# MoteinoR5USB-LP.net
KiCad netlist of a schematic drawn in EAGLE
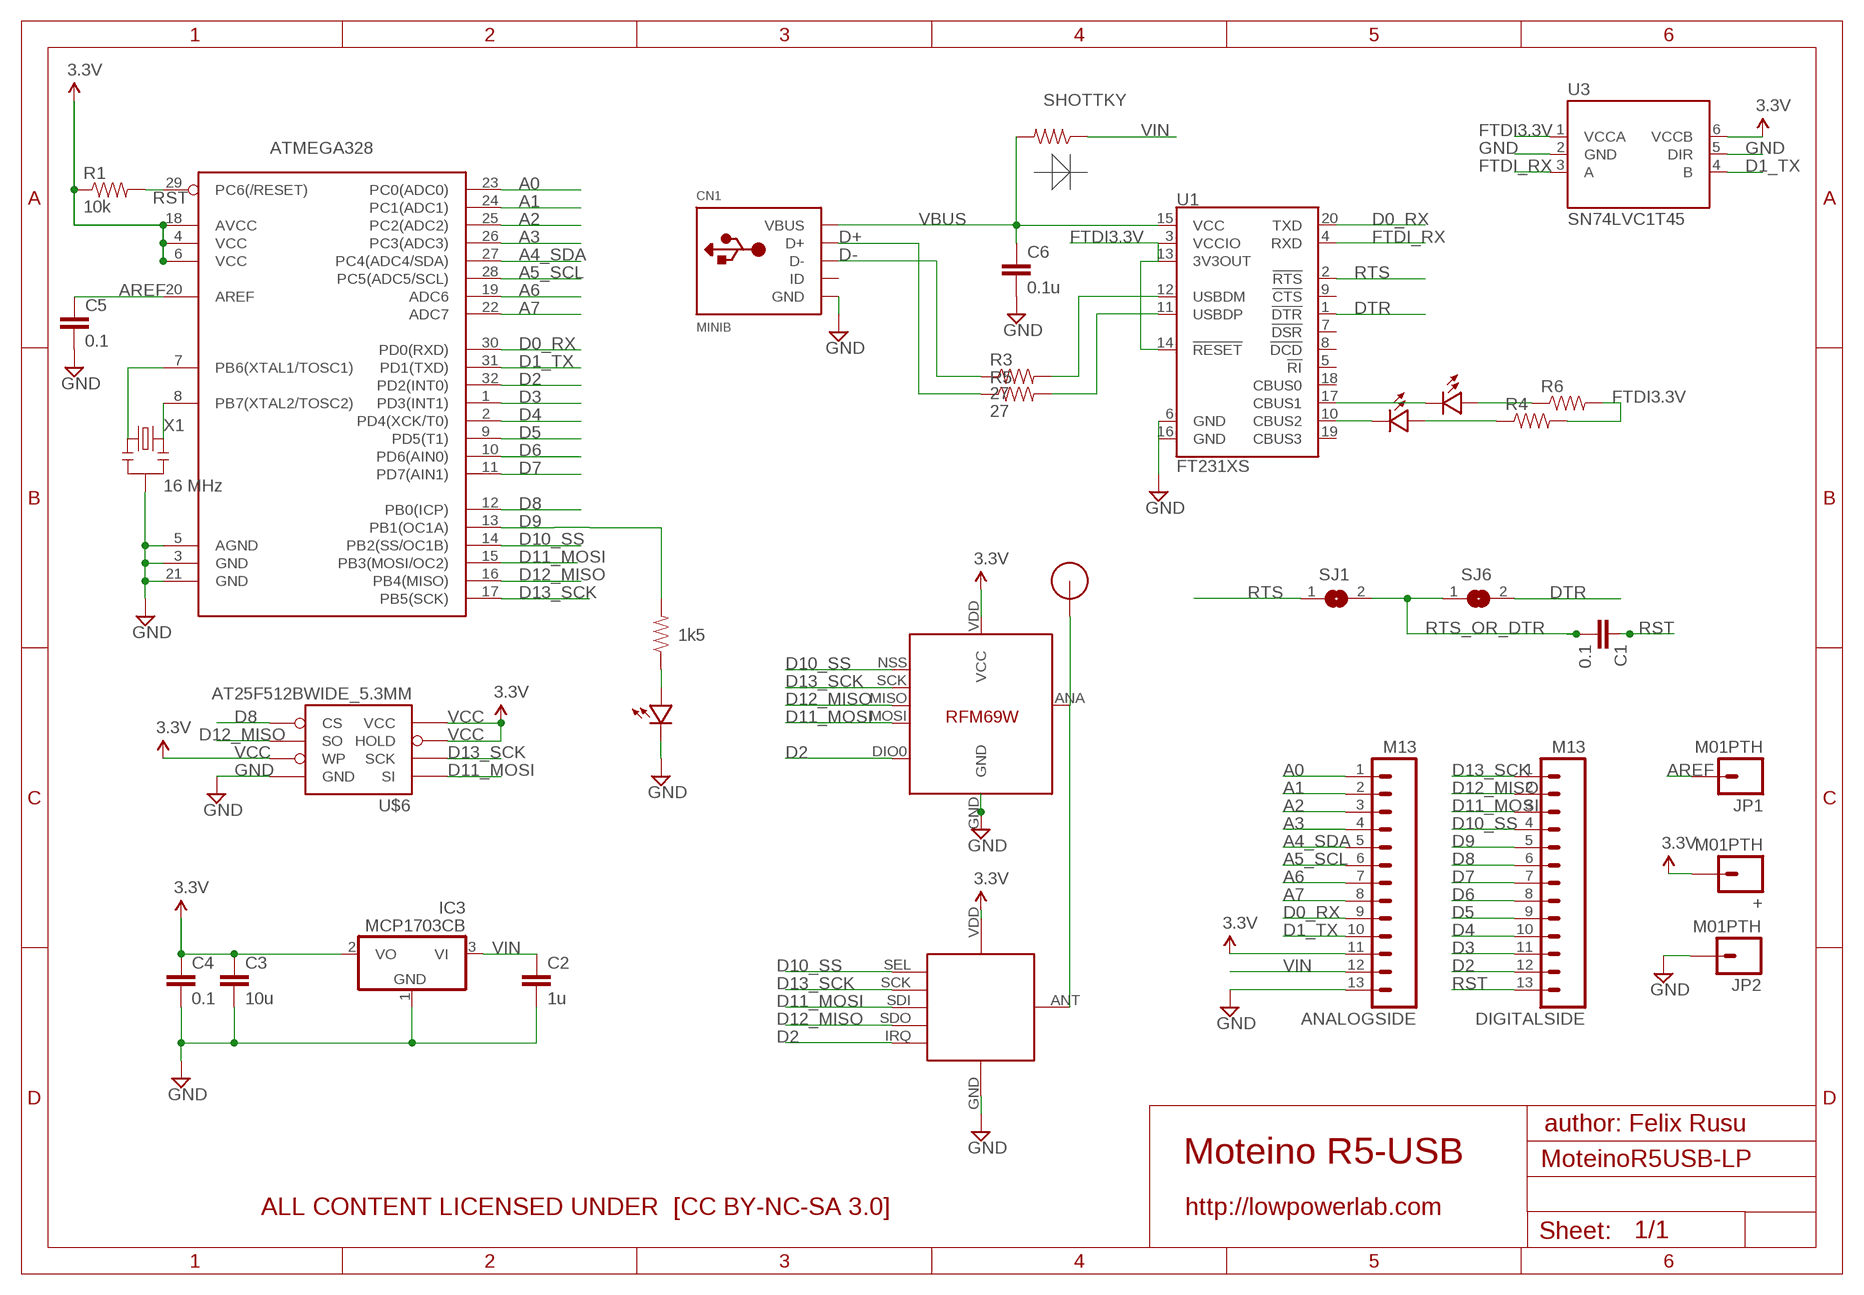
[diagram p0: schematic, sheet 1]

(export (version "E")
  (design (tool "Eeschema 10.0.6"))
  (components
    (comp (ref "+")
      (value "M01PTH")
      (footprint "eagle-import:1X01")
      (libsource (lib "eagle-import") (part "M01PTH"))
    )
    (comp (ref "ANALOGSIDE")
      (value "M13")
      (footprint "eagle-import:1X13")
      (libsource (lib "eagle-import") (part "M13"))
    )
    (comp (ref "ATMEGA328")
      (value "ATMega-328")
      (footprint "eagle-import:TQFP32-08")
      (libsource (lib "eagle-import") (part "ATMEGA168/328TQFP32"))
    )
    (comp (ref "C1")
      (value "0.1")
      (footprint "eagle-import:0603-CAP")
      (libsource (lib "eagle-import") (part "CAP0603-CAP"))
    )
    (comp (ref "C2")
      (value "1u")
      (footprint "eagle-import:0603-CAP")
      (libsource (lib "eagle-import") (part "CAP0603-CAP"))
    )
    (comp (ref "C3")
      (value "10u")
      (footprint "eagle-import:0805-CAP")
      (libsource (lib "eagle-import") (part "CAP0805-CAP"))
    )
    (comp (ref "C4")
      (value "0.1")
      (footprint "eagle-import:0603-CAP")
      (libsource (lib "eagle-import") (part "CAP0603-CAP"))
    )
    (comp (ref "C5")
      (value "0.1")
      (footprint "eagle-import:0603-CAP")
      (libsource (lib "eagle-import") (part "CAP0603-CAP"))
    )
    (comp (ref "C6")
      (value "0.1u")
      (footprint "eagle-import:0603-CAP")
      (libsource (lib "eagle-import") (part "CAP0603-CAP"))
    )
    (comp (ref "CN1")
      (value "MINIB")
      (footprint "eagle-import:USB-MINIB")
      (libsource (lib "eagle-import") (part "USBMINIB"))
    )
    (comp (ref "D")
      (value "SHOTTKY")
      (footprint "eagle-import:0603-RES")
      (libsource (lib "eagle-import") (part "RESISTOR0603-RES"))
    )
    (comp (ref "DIGITALSIDE")
      (value "M13")
      (footprint "eagle-import:1X13")
      (libsource (lib "eagle-import") (part "M13"))
    )
    (comp (ref "IC3")
      (value "MCP1703CB")
      (footprint "eagle-import:SOT23")
      (libsource (lib "eagle-import") (part "MCP1703CB"))
    )
    (comp (ref "JP1")
      (value "M01PTH")
      (footprint "eagle-import:1X01")
      (libsource (lib "eagle-import") (part "M01PTH"))
    )
    (comp (ref "JP2")
      (value "M01PTH")
      (footprint "eagle-import:1X01")
      (libsource (lib "eagle-import") (part "M01PTH"))
    )
    (comp (ref "R1")
      (value "10k")
      (footprint "eagle-import:0603-RES")
      (libsource (lib "eagle-import") (part "RESISTOR0603-RES"))
    )
    (comp (ref "R2")
      (value "1k5")
      (footprint "eagle-import:0603-RES")
      (libsource (lib "eagle-import") (part "RESISTOR0603-RES"))
    )
    (comp (ref "R3")
      (value "27")
      (footprint "eagle-import:0603-RES")
      (libsource (lib "eagle-import") (part "RESISTOR0603-RES"))
    )
    (comp (ref "R4")
      (value "RESISTOR0603-RES")
      (footprint "eagle-import:0603-RES")
      (libsource (lib "eagle-import") (part "RESISTOR0603-RES"))
    )
    (comp (ref "R5")
      (value "27")
      (footprint "eagle-import:0603-RES")
      (libsource (lib "eagle-import") (part "RESISTOR0603-RES"))
    )
    (comp (ref "R6")
      (value "RESISTOR0603-RES")
      (footprint "eagle-import:0603-RES")
      (libsource (lib "eagle-import") (part "RESISTOR0603-RES"))
    )
    (comp (ref "RFM12B")
      (value "RFM12B_MINPADS")
      (footprint "eagle-import:RFM12B-MINPADS")
      (libsource (lib "eagle-import") (part "RFM12B_MINPADS"))
    )
    (comp (ref "SJ1")
      (value "JUMPER")
      (footprint "eagle-import:SJW")
      (libsource (lib "eagle-import") (part "JUMPER"))
    )
    (comp (ref "SJ6")
      (value "JUMPER")
      (footprint "eagle-import:SJW")
      (libsource (lib "eagle-import") (part "JUMPER"))
    )
    (comp (ref "U$1")
      (value "RFM12B_ANTENNA")
      (footprint "eagle-import:RFM12B-ANTENNA")
      (libsource (lib "eagle-import") (part "RFM12B_ANTENNA"))
    )
    (comp (ref "U$2")
      (value "LED0603")
      (footprint "eagle-import:0603-LED")
      (libsource (lib "eagle-import") (part "LED0603"))
    )
    (comp (ref "U$4")
      (value "LED0603")
      (footprint "eagle-import:0603-LED")
      (libsource (lib "eagle-import") (part "LED0603"))
    )
    (comp (ref "U$5")
      (value "RFM69")
      (footprint "eagle-import:RFM69W-MINPADS")
      (libsource (lib "eagle-import") (part "RFM69"))
    )
    (comp (ref "U$6")
      (value "AT25F512BWIDE_5.3MM")
      (footprint "eagle-import:SO08WIDE")
      (libsource (lib "eagle-import") (part "AT25F512BWIDE_5.3MM"))
    )
    (comp (ref "U$7")
      (value "LED0603")
      (footprint "eagle-import:0603-LED")
      (libsource (lib "eagle-import") (part "LED0603"))
    )
    (comp (ref "U1")
      (value "FT231XS")
      (footprint "eagle-import:SSOP20_L")
      (libsource (lib "eagle-import") (part "FT231XS"))
    )
    (comp (ref "U3")
      (value "SN74LVC1T45")
      (footprint "eagle-import:SOT23-6")
      (libsource (lib "eagle-import") (part "SN74LVC1T45SOT-23"))
    )
    (comp (ref "X1")
      (value "16 MHz")
      (footprint "eagle-import:RESONATOR-SMD")
      (libsource (lib "eagle-import") (part "RESONATORSMD"))
    )
  )
  (nets
    (net (code "1") (name "/A0") (class "Default")
      (node (ref "ANALOGSIDE") (pin "1") (pinfunction "1_1") (pintype "passive"))
      (node (ref "ATMEGA328") (pin "23") (pinfunction "PC0(ADC0)_23") (pintype "bidirectional"))
    )
    (net (code "2") (name "/A1") (class "Default")
      (node (ref "ANALOGSIDE") (pin "2") (pinfunction "2_2") (pintype "passive"))
      (node (ref "ATMEGA328") (pin "24") (pinfunction "PC1(ADC1)_24") (pintype "bidirectional"))
    )
    (net (code "3") (name "/A2") (class "Default")
      (node (ref "ANALOGSIDE") (pin "3") (pinfunction "3_3") (pintype "passive"))
      (node (ref "ATMEGA328") (pin "25") (pinfunction "PC2(ADC2)_25") (pintype "bidirectional"))
    )
    (net (code "4") (name "/A3") (class "Default")
      (node (ref "ANALOGSIDE") (pin "4") (pinfunction "4_4") (pintype "passive"))
      (node (ref "ATMEGA328") (pin "26") (pinfunction "PC3(ADC3)_26") (pintype "bidirectional"))
    )
    (net (code "5") (name "/A4_SDA") (class "Default")
      (node (ref "ANALOGSIDE") (pin "5") (pinfunction "5_5") (pintype "passive"))
      (node (ref "ATMEGA328") (pin "27") (pinfunction "PC4(ADC4/SDA)_27") (pintype "bidirectional"))
    )
    (net (code "6") (name "/A5_SCL") (class "Default")
      (node (ref "ANALOGSIDE") (pin "6") (pinfunction "6_6") (pintype "passive"))
      (node (ref "ATMEGA328") (pin "28") (pinfunction "PC5(ADC5/SCL)_28") (pintype "bidirectional"))
    )
    (net (code "7") (name "/A6") (class "Default")
      (node (ref "ANALOGSIDE") (pin "7") (pinfunction "7_7") (pintype "passive"))
      (node (ref "ATMEGA328") (pin "19") (pinfunction "ADC6_19") (pintype "bidirectional"))
    )
    (net (code "8") (name "/A7") (class "Default")
      (node (ref "ANALOGSIDE") (pin "8") (pinfunction "8_8") (pintype "passive"))
      (node (ref "ATMEGA328") (pin "22") (pinfunction "ADC7_22") (pintype "bidirectional"))
    )
    (net (code "9") (name "/AREF") (class "Default")
      (node (ref "ATMEGA328") (pin "20") (pinfunction "AREF_20") (pintype "bidirectional"))
      (node (ref "C5") (pin "1") (pinfunction "1_1") (pintype "passive"))
      (node (ref "JP1") (pin "1") (pinfunction "1_1") (pintype "passive"))
    )
    (net (code "10") (name "/D+") (class "Default")
      (node (ref "CN1") (pin "D+") (pinfunction "D+_D+") (pintype "bidirectional"))
      (node (ref "R5") (pin "1") (pinfunction "1_1") (pintype "passive"))
    )
    (net (code "11") (name "/D-") (class "Default")
      (node (ref "CN1") (pin "D-") (pinfunction "D-_D-") (pintype "bidirectional"))
      (node (ref "R3") (pin "1") (pinfunction "1_1") (pintype "passive"))
    )
    (net (code "12") (name "/D0_RX") (class "Default")
      (node (ref "ANALOGSIDE") (pin "9") (pinfunction "9_9") (pintype "passive"))
      (node (ref "ATMEGA328") (pin "30") (pinfunction "PD0(RXD)_30") (pintype "bidirectional"))
      (node (ref "U1") (pin "20") (pinfunction "TXD_20") (pintype "bidirectional"))
    )
    (net (code "13") (name "/D1_TX") (class "Default")
      (node (ref "ANALOGSIDE") (pin "10") (pinfunction "10_10") (pintype "passive"))
      (node (ref "ATMEGA328") (pin "31") (pinfunction "PD1(TXD)_31") (pintype "bidirectional"))
      (node (ref "U3") (pin "4") (pinfunction "B_4") (pintype "bidirectional"))
    )
    (net (code "14") (name "/D2") (class "Default")
      (node (ref "ATMEGA328") (pin "32") (pinfunction "PD2(INT0)_32") (pintype "bidirectional"))
      (node (ref "DIGITALSIDE") (pin "12") (pinfunction "12_12") (pintype "passive"))
      (node (ref "RFM12B") (pin "IRQ") (pinfunction "IRQ_IRQ") (pintype "bidirectional"))
      (node (ref "U$5") (pin "DIO0") (pinfunction "DIO0_DIO0") (pintype "open_collector"))
    )
    (net (code "15") (name "/D3") (class "Default")
      (node (ref "ATMEGA328") (pin "1") (pinfunction "PD3(INT1)_1") (pintype "bidirectional"))
      (node (ref "DIGITALSIDE") (pin "11") (pinfunction "11_11") (pintype "passive"))
    )
    (net (code "16") (name "/D4") (class "Default")
      (node (ref "ATMEGA328") (pin "2") (pinfunction "PD4(XCK/T0)_2") (pintype "bidirectional"))
      (node (ref "DIGITALSIDE") (pin "10") (pinfunction "10_10") (pintype "passive"))
    )
    (net (code "17") (name "/D5") (class "Default")
      (node (ref "ATMEGA328") (pin "9") (pinfunction "PD5(T1)_9") (pintype "bidirectional"))
      (node (ref "DIGITALSIDE") (pin "9") (pinfunction "9_9") (pintype "passive"))
    )
    (net (code "18") (name "/D6") (class "Default")
      (node (ref "ATMEGA328") (pin "10") (pinfunction "PD6(AIN0)_10") (pintype "bidirectional"))
      (node (ref "DIGITALSIDE") (pin "8") (pinfunction "8_8") (pintype "passive"))
    )
    (net (code "19") (name "/D7") (class "Default")
      (node (ref "ATMEGA328") (pin "11") (pinfunction "PD7(AIN1)_11") (pintype "bidirectional"))
      (node (ref "DIGITALSIDE") (pin "7") (pinfunction "7_7") (pintype "passive"))
    )
    (net (code "20") (name "/D8") (class "Default")
      (node (ref "ATMEGA328") (pin "12") (pinfunction "PB0(ICP)_12") (pintype "bidirectional"))
      (node (ref "DIGITALSIDE") (pin "6") (pinfunction "6_6") (pintype "passive"))
      (node (ref "U$6") (pin "1") (pinfunction "CS_1") (pintype "bidirectional"))
    )
    (net (code "21") (name "/D9") (class "Default")
      (node (ref "ATMEGA328") (pin "13") (pinfunction "PB1(OC1A)_13") (pintype "bidirectional"))
      (node (ref "DIGITALSIDE") (pin "5") (pinfunction "5_5") (pintype "passive"))
      (node (ref "R2") (pin "2") (pinfunction "2_2") (pintype "passive"))
    )
    (net (code "22") (name "/D10_SS") (class "Default")
      (node (ref "ATMEGA328") (pin "14") (pinfunction "PB2(SS/OC1B)_14") (pintype "bidirectional"))
      (node (ref "DIGITALSIDE") (pin "4") (pinfunction "4_4") (pintype "passive"))
      (node (ref "RFM12B") (pin "SEL") (pinfunction "SEL_SEL") (pintype "bidirectional"))
      (node (ref "U$5") (pin "NSS") (pinfunction "SEL_NSS") (pintype "input"))
    )
    (net (code "23") (name "/D11_MOSI") (class "Default")
      (node (ref "ATMEGA328") (pin "15") (pinfunction "PB3(MOSI/OC2)_15") (pintype "bidirectional"))
      (node (ref "DIGITALSIDE") (pin "3") (pinfunction "3_3") (pintype "passive"))
      (node (ref "RFM12B") (pin "SDI") (pinfunction "SDI/MOSI_SDI") (pintype "bidirectional"))
      (node (ref "U$5") (pin "MOSI") (pinfunction "MOSI_MOSI") (pintype "output"))
      (node (ref "U$6") (pin "5") (pinfunction "SI_5") (pintype "bidirectional"))
    )
    (net (code "24") (name "/D12_MISO") (class "Default")
      (node (ref "ATMEGA328") (pin "16") (pinfunction "PB4(MISO)_16") (pintype "bidirectional"))
      (node (ref "DIGITALSIDE") (pin "2") (pinfunction "2_2") (pintype "passive"))
      (node (ref "RFM12B") (pin "SDO") (pinfunction "SDO/MISO_SDO") (pintype "bidirectional"))
      (node (ref "U$5") (pin "MISO") (pinfunction "MISO_MISO") (pintype "input"))
      (node (ref "U$6") (pin "2") (pinfunction "SO_2") (pintype "bidirectional"))
    )
    (net (code "25") (name "/D13_SCK") (class "Default")
      (node (ref "ATMEGA328") (pin "17") (pinfunction "PB5(SCK)_17") (pintype "bidirectional"))
      (node (ref "DIGITALSIDE") (pin "1") (pinfunction "1_1") (pintype "passive"))
      (node (ref "RFM12B") (pin "SCK") (pinfunction "SCK_SCK") (pintype "bidirectional"))
      (node (ref "U$5") (pin "SCK") (pinfunction "SCK_SCK") (pintype "input"))
      (node (ref "U$6") (pin "6") (pinfunction "SCK_6") (pintype "bidirectional"))
    )
    (net (code "26") (name "/DTR") (class "Default")
      (node (ref "SJ6") (pin "2") (pinfunction "2_2") (pintype "passive"))
      (node (ref "U1") (pin "1") (pinfunction "~{DTR}_1") (pintype "bidirectional"))
    )
    (net (code "27") (name "/FTDI3.3V") (class "Default")
      (node (ref "R4") (pin "2") (pinfunction "2_2") (pintype "passive"))
      (node (ref "R6") (pin "2") (pinfunction "2_2") (pintype "passive"))
      (node (ref "U1") (pin "13") (pinfunction "3V3OUT_13") (pintype "bidirectional"))
      (node (ref "U1") (pin "14") (pinfunction "~{RESET}_14") (pintype "bidirectional"))
      (node (ref "U1") (pin "3") (pinfunction "VCCIO_3") (pintype "bidirectional"))
      (node (ref "U3") (pin "1") (pinfunction "VCCA_1") (pintype "bidirectional"))
    )
    (net (code "28") (name "/FTDI_RX") (class "Default")
      (node (ref "U1") (pin "4") (pinfunction "RXD_4") (pintype "bidirectional"))
      (node (ref "U3") (pin "3") (pinfunction "A_3") (pintype "bidirectional"))
    )
    (net (code "29") (name "/RST") (class "Default")
      (node (ref "ATMEGA328") (pin "29") (pinfunction "PC6(/RESET)_29") (pintype "bidirectional"))
      (node (ref "C1") (pin "1") (pinfunction "1_1") (pintype "passive"))
      (node (ref "DIGITALSIDE") (pin "13") (pinfunction "13_13") (pintype "passive"))
      (node (ref "R1") (pin "2") (pinfunction "2_2") (pintype "passive"))
    )
    (net (code "30") (name "/RTS") (class "Default")
      (node (ref "SJ1") (pin "1") (pinfunction "1_1") (pintype "passive"))
      (node (ref "U1") (pin "2") (pinfunction "~{RTS}_2") (pintype "bidirectional"))
    )
    (net (code "31") (name "/RTS_OR_DTR") (class "Default")
      (node (ref "C1") (pin "2") (pinfunction "2_2") (pintype "passive"))
      (node (ref "SJ1") (pin "2") (pinfunction "2_2") (pintype "passive"))
      (node (ref "SJ6") (pin "1") (pinfunction "1_1") (pintype "passive"))
    )
    (net (code "32") (name "/VBUS") (class "Default")
      (node (ref "C6") (pin "1") (pinfunction "1_1") (pintype "passive"))
      (node (ref "CN1") (pin "VBUS") (pinfunction "VBUS_VBUS") (pintype "power_in"))
      (node (ref "D") (pin "2") (pinfunction "2_2") (pintype "passive"))
      (node (ref "U1") (pin "15") (pinfunction "VCC_15") (pintype "bidirectional"))
    )
    (net (code "33") (name "/VIN") (class "Default")
      (node (ref "ANALOGSIDE") (pin "12") (pinfunction "12_12") (pintype "passive"))
      (node (ref "C2") (pin "1") (pinfunction "1_1") (pintype "passive"))
      (node (ref "D") (pin "1") (pinfunction "1_1") (pintype "passive"))
      (node (ref "IC3") (pin "3") (pinfunction "VI_3") (pintype "input"))
    )
    (net (code "34") (name "3.3V") (class "Default")
      (node (ref "+") (pin "1") (pinfunction "1_1") (pintype "passive"))
      (node (ref "ANALOGSIDE") (pin "11") (pinfunction "11_11") (pintype "passive"))
      (node (ref "ATMEGA328") (pin "18") (pinfunction "AVCC_18") (pintype "bidirectional"))
      (node (ref "ATMEGA328") (pin "4") (pinfunction "VCC_4") (pintype "bidirectional"))
      (node (ref "ATMEGA328") (pin "6") (pinfunction "VCC_6") (pintype "bidirectional"))
      (node (ref "C3") (pin "1") (pinfunction "1_1") (pintype "passive"))
      (node (ref "C4") (pin "1") (pinfunction "1_1") (pintype "passive"))
      (node (ref "IC3") (pin "2") (pinfunction "VO_2") (pintype "passive"))
      (node (ref "R1") (pin "1") (pinfunction "1_1") (pintype "passive"))
      (node (ref "RFM12B") (pin "VDD") (pinfunction "VDD_VDD") (pintype "bidirectional"))
      (node (ref "U$5") (pin "VDD") (pinfunction "VCC_VDD") (pintype "power_in"))
      (node (ref "U$6") (pin "3") (pinfunction "WP_3") (pintype "bidirectional"))
      (node (ref "U$6") (pin "7") (pinfunction "HOLD_7") (pintype "bidirectional"))
      (node (ref "U$6") (pin "8") (pinfunction "VCC_8") (pintype "bidirectional"))
      (node (ref "U3") (pin "6") (pinfunction "VCCB_6") (pintype "bidirectional"))
    )
    (net (code "35") (name "GND") (class "Default")
      (node (ref "ANALOGSIDE") (pin "13") (pinfunction "13_13") (pintype "passive"))
      (node (ref "ATMEGA328") (pin "21") (pinfunction "GND_21") (pintype "bidirectional"))
      (node (ref "ATMEGA328") (pin "3") (pinfunction "GND_3") (pintype "bidirectional"))
      (node (ref "ATMEGA328") (pin "5") (pinfunction "AGND_5") (pintype "bidirectional"))
      (node (ref "C2") (pin "2") (pinfunction "2_2") (pintype "passive"))
      (node (ref "C3") (pin "2") (pinfunction "2_2") (pintype "passive"))
      (node (ref "C4") (pin "2") (pinfunction "2_2") (pintype "passive"))
      (node (ref "C5") (pin "2") (pinfunction "2_2") (pintype "passive"))
      (node (ref "C6") (pin "2") (pinfunction "2_2") (pintype "passive"))
      (node (ref "CN1") (pin "GND") (pinfunction "GND_GND") (pintype "power_in"))
      (node (ref "IC3") (pin "1") (pinfunction "GND_1") (pintype "passive"))
      (node (ref "JP2") (pin "1") (pinfunction "1_1") (pintype "passive"))
      (node (ref "RFM12B") (pin "GND") (pinfunction "GND_GND") (pintype "bidirectional"))
      (node (ref "U$2") (pin "MINUS") (pinfunction "MINUS_MINUS") (pintype "passive"))
      (node (ref "U$5") (pin "GND") (pinfunction "GND_GND") (pintype "power_in"))
      (node (ref "U$6") (pin "4") (pinfunction "GND_4") (pintype "bidirectional"))
      (node (ref "U1") (pin "16") (pinfunction "GND_16") (pintype "bidirectional"))
      (node (ref "U1") (pin "6") (pinfunction "GND_6") (pintype "bidirectional"))
      (node (ref "U3") (pin "2") (pinfunction "GND_2") (pintype "bidirectional"))
      (node (ref "U3") (pin "5") (pinfunction "DIR_5") (pintype "bidirectional"))
      (node (ref "X1") (pin "2") (pinfunction "2_2") (pintype "passive"))
    )
    (net (code "36") (name "Net-(ATMEGA328-PB6(XTAL1{slash}TOSC1))") (class "Default")
      (node (ref "ATMEGA328") (pin "7") (pinfunction "PB6(XTAL1/TOSC1)_7") (pintype "bidirectional"))
      (node (ref "X1") (pin "1") (pinfunction "1_1") (pintype "passive"))
    )
    (net (code "37") (name "Net-(ATMEGA328-PB7(XTAL2{slash}TOSC2))") (class "Default")
      (node (ref "ATMEGA328") (pin "8") (pinfunction "PB7(XTAL2/TOSC2)_8") (pintype "bidirectional"))
      (node (ref "X1") (pin "3") (pinfunction "3_3") (pintype "passive"))
    )
    (net (code "38") (name "Net-(R2-Pad1)") (class "Default")
      (node (ref "R2") (pin "1") (pinfunction "1_1") (pintype "passive"))
      (node (ref "U$2") (pin "PLUS") (pinfunction "PLUS_PLUS") (pintype "passive"))
    )
    (net (code "39") (name "Net-(R4-Pad1)") (class "Default")
      (node (ref "R4") (pin "1") (pinfunction "1_1") (pintype "passive"))
      (node (ref "U$7") (pin "PLUS") (pinfunction "PLUS_PLUS") (pintype "passive"))
    )
    (net (code "40") (name "Net-(R6-Pad1)") (class "Default")
      (node (ref "R6") (pin "1") (pinfunction "1_1") (pintype "passive"))
      (node (ref "U$4") (pin "PLUS") (pinfunction "PLUS_PLUS") (pintype "passive"))
    )
    (net (code "41") (name "Net-(U$1-1)") (class "Default")
      (node (ref "RFM12B") (pin "ANT") (pinfunction "ANT_ANT") (pintype "bidirectional"))
      (node (ref "U$1") (pin "P$1") (pinfunction "1_P$1") (pintype "bidirectional"))
      (node (ref "U$5") (pin "ANA") (pinfunction "ANT_ANA") (pintype "passive"))
    )
    (net (code "42") (name "Net-(U1-CBUS1)") (class "Default")
      (node (ref "U$4") (pin "MINUS") (pinfunction "MINUS_MINUS") (pintype "passive"))
      (node (ref "U1") (pin "17") (pinfunction "CBUS1_17") (pintype "bidirectional"))
    )
    (net (code "43") (name "Net-(U1-CBUS2)") (class "Default")
      (node (ref "U$7") (pin "MINUS") (pinfunction "MINUS_MINUS") (pintype "passive"))
      (node (ref "U1") (pin "10") (pinfunction "CBUS2_10") (pintype "bidirectional"))
    )
    (net (code "44") (name "Net-(U1-USBDM)") (class "Default")
      (node (ref "R3") (pin "2") (pinfunction "2_2") (pintype "passive"))
      (node (ref "U1") (pin "12") (pinfunction "USBDM_12") (pintype "bidirectional"))
    )
    (net (code "45") (name "Net-(U1-USBDP)") (class "Default")
      (node (ref "R5") (pin "2") (pinfunction "2_2") (pintype "passive"))
      (node (ref "U1") (pin "11") (pinfunction "USBDP_11") (pintype "bidirectional"))
    )
    (net (code "46") (name "unconnected-(CN1-PadID)") (class "Default")
      (node (ref "CN1") (pin "ID") (pinfunction "ID_ID") (pintype "bidirectional"))
    )
    (net (code "47") (name "unconnected-(U1-CBUS0-Pad18)") (class "Default")
      (node (ref "U1") (pin "18") (pinfunction "CBUS0_18") (pintype "bidirectional"))
    )
    (net (code "48") (name "unconnected-(U1-CBUS3-Pad19)") (class "Default")
      (node (ref "U1") (pin "19") (pinfunction "CBUS3_19") (pintype "bidirectional"))
    )
    (net (code "49") (name "unconnected-(U1-~{CTS}-Pad9)") (class "Default")
      (node (ref "U1") (pin "9") (pinfunction "~{CTS}_9") (pintype "bidirectional"))
    )
    (net (code "50") (name "unconnected-(U1-~{DCD}-Pad8)") (class "Default")
      (node (ref "U1") (pin "8") (pinfunction "~{DCD}_8") (pintype "bidirectional"))
    )
    (net (code "51") (name "unconnected-(U1-~{DSR}-Pad7)") (class "Default")
      (node (ref "U1") (pin "7") (pinfunction "~{DSR}_7") (pintype "bidirectional"))
    )
    (net (code "52") (name "unconnected-(U1-~{RI}-Pad5)") (class "Default")
      (node (ref "U1") (pin "5") (pinfunction "~{RI}_5") (pintype "bidirectional"))
    )
  )
)
